# BLUELED.net
KiCad netlist of a schematic drawn in Altium Designer
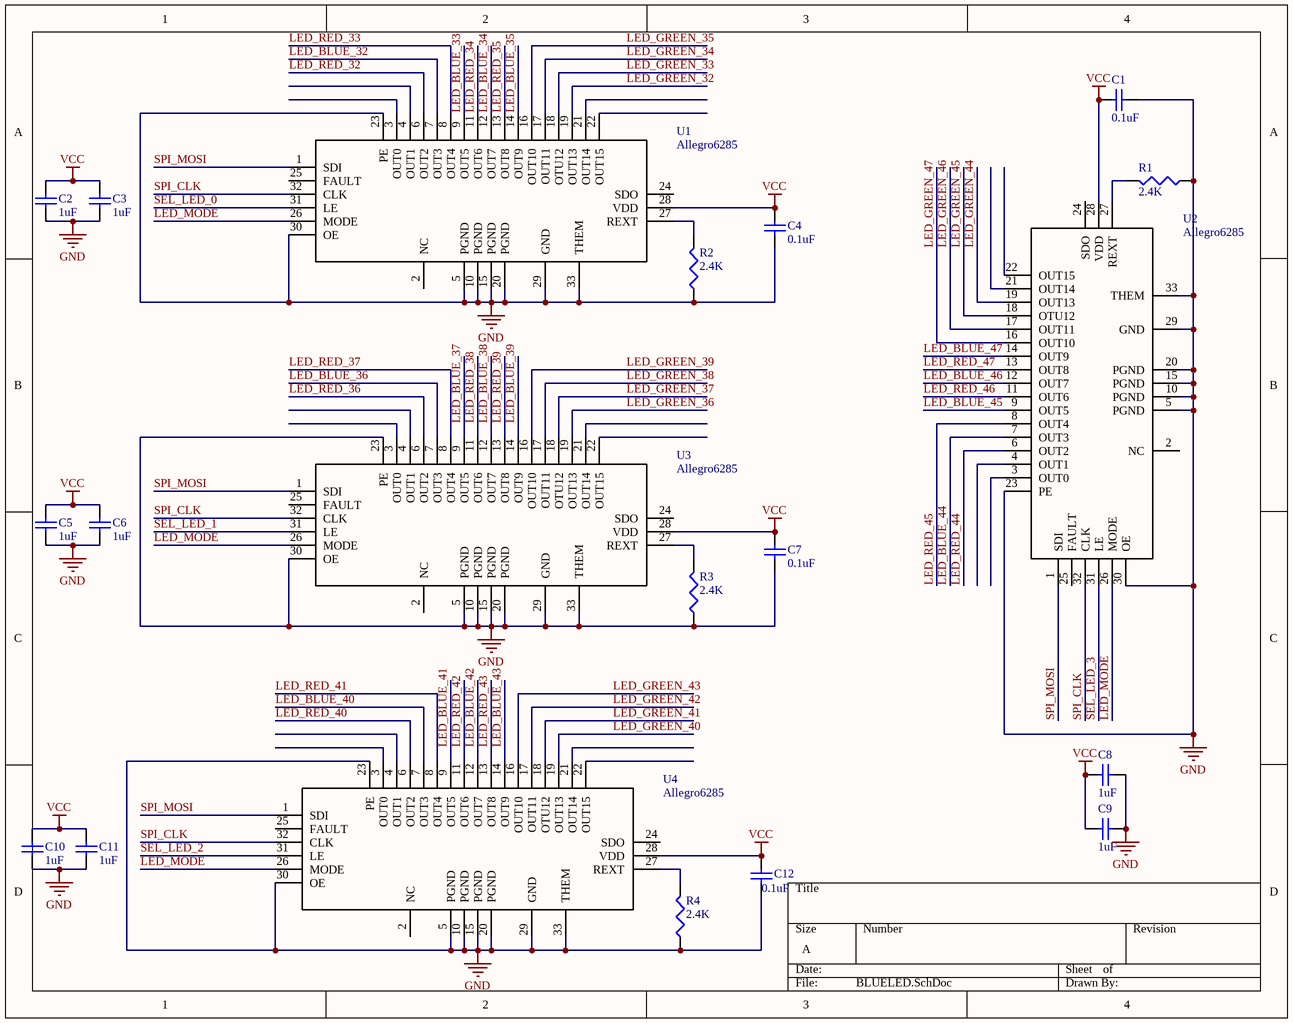
[diagram p0: BLUELED.SchDoc]

(export (version "E")
  (design (tool "Eeschema 10.0.6"))
  (components
    (comp (ref "C1")
      (value "0.1uF")
      (footprint "CAPC1005L")
      (description "Capacitor (Semiconductor SIM Model)")
      (fields (field (name "Comment") "Cap Semi") (field (name "PUBLISHER") "Altium Limited"))
      (libsource (lib "Miscellaneous Devices") (part "Cap Semi"))
    )
    (comp (ref "C2")
      (value "1uF")
      (footprint "CAPC1608L")
      (description "Capacitor (Semiconductor SIM Model)")
      (fields (field (name "Comment") "Cap Semi") (field (name "PUBLISHER") "Altium Limited"))
      (libsource (lib "Miscellaneous Devices") (part "Cap Semi"))
    )
    (comp (ref "C3")
      (value "1uF")
      (footprint "CAPC1608L")
      (description "Capacitor (Semiconductor SIM Model)")
      (fields (field (name "Comment") "Cap Semi") (field (name "PUBLISHER") "Altium Limited"))
      (libsource (lib "Miscellaneous Devices") (part "Cap Semi"))
    )
    (comp (ref "C4")
      (value "0.1uF")
      (footprint "CAPC1005L")
      (description "Capacitor (Semiconductor SIM Model)")
      (fields (field (name "Comment") "Cap Semi") (field (name "PUBLISHER") "Altium Limited"))
      (libsource (lib "Miscellaneous Devices") (part "Cap Semi"))
    )
    (comp (ref "C5")
      (value "1uF")
      (footprint "CAPC1608L")
      (description "Capacitor (Semiconductor SIM Model)")
      (fields (field (name "Comment") "Cap Semi") (field (name "PUBLISHER") "Altium Limited"))
      (libsource (lib "Miscellaneous Devices") (part "Cap Semi"))
    )
    (comp (ref "C6")
      (value "1uF")
      (footprint "CAPC1608L")
      (description "Capacitor (Semiconductor SIM Model)")
      (fields (field (name "Comment") "Cap Semi") (field (name "PUBLISHER") "Altium Limited"))
      (libsource (lib "Miscellaneous Devices") (part "Cap Semi"))
    )
    (comp (ref "C7")
      (value "0.1uF")
      (footprint "CAPC1005L")
      (description "Capacitor (Semiconductor SIM Model)")
      (fields (field (name "Comment") "Cap Semi") (field (name "PUBLISHER") "Altium Limited"))
      (libsource (lib "Miscellaneous Devices") (part "Cap Semi"))
    )
    (comp (ref "C8")
      (value "1uF")
      (footprint "CAPC1608L")
      (description "Capacitor (Semiconductor SIM Model)")
      (fields (field (name "Comment") "Cap Semi") (field (name "PUBLISHER") "Altium Limited"))
      (libsource (lib "Miscellaneous Devices") (part "Cap Semi"))
    )
    (comp (ref "C9")
      (value "1uF")
      (footprint "CAPC1608L")
      (description "Capacitor (Semiconductor SIM Model)")
      (fields (field (name "Comment") "Cap Semi") (field (name "PUBLISHER") "Altium Limited"))
      (libsource (lib "Miscellaneous Devices") (part "Cap Semi"))
    )
    (comp (ref "C10")
      (value "1uF")
      (footprint "CAPC1608L")
      (description "Capacitor (Semiconductor SIM Model)")
      (fields (field (name "Comment") "Cap Semi") (field (name "PUBLISHER") "Altium Limited"))
      (libsource (lib "Miscellaneous Devices") (part "Cap Semi"))
    )
    (comp (ref "C11")
      (value "1uF")
      (footprint "CAPC1608L")
      (description "Capacitor (Semiconductor SIM Model)")
      (fields (field (name "Comment") "Cap Semi") (field (name "PUBLISHER") "Altium Limited"))
      (libsource (lib "Miscellaneous Devices") (part "Cap Semi"))
    )
    (comp (ref "C12")
      (value "0.1uF")
      (footprint "CAPC1005L")
      (description "Capacitor (Semiconductor SIM Model)")
      (fields (field (name "Comment") "Cap Semi") (field (name "PUBLISHER") "Altium Limited"))
      (libsource (lib "Miscellaneous Devices") (part "Cap Semi"))
    )
    (comp (ref "R1")
      (value "2.4K")
      (footprint "RESC1608L")
      (description "Resistor")
      (fields (field (name "Comment") "Res3") (field (name "PUBLISHER") "Altium Limited"))
      (libsource (lib "Miscellaneous Devices") (part "Res3"))
    )
    (comp (ref "R2")
      (value "2.4K")
      (footprint "RESC1608L")
      (description "Resistor")
      (fields (field (name "Comment") "Res3") (field (name "PUBLISHER") "Altium Limited"))
      (libsource (lib "Miscellaneous Devices") (part "Res3"))
    )
    (comp (ref "R3")
      (value "2.4K")
      (footprint "RESC1608L")
      (description "Resistor")
      (fields (field (name "Comment") "Res3") (field (name "PUBLISHER") "Altium Limited"))
      (libsource (lib "Miscellaneous Devices") (part "Res3"))
    )
    (comp (ref "R4")
      (value "2.4K")
      (footprint "RESC1608L")
      (description "Resistor")
      (fields (field (name "Comment") "Res3") (field (name "PUBLISHER") "Altium Limited"))
      (libsource (lib "Miscellaneous Devices") (part "Res3"))
    )
    (comp (ref "U1")
      (value "Allegro6285")
      (footprint "QFN-32")
      (libsource (lib "mrone") (part "Allegro6285"))
    )
    (comp (ref "U2")
      (value "Allegro6285")
      (footprint "QFN-32")
      (libsource (lib "mrone") (part "Allegro6285"))
    )
    (comp (ref "U3")
      (value "Allegro6285")
      (footprint "QFN-32")
      (libsource (lib "mrone") (part "Allegro6285"))
    )
    (comp (ref "U4")
      (value "Allegro6285")
      (footprint "QFN-32")
      (libsource (lib "mrone") (part "Allegro6285"))
    )
  )
  (nets
    (net (code "1") (name "/LED_BLUE_32") (class "Default")
      (node (ref "U1") (pin "7") (pinfunction "OUT3_7") (pintype "passive"))
    )
    (net (code "2") (name "/LED_BLUE_33") (class "Default")
      (node (ref "U1") (pin "9") (pinfunction "OUT5_9") (pintype "passive"))
    )
    (net (code "3") (name "/LED_BLUE_34") (class "Default")
      (node (ref "U1") (pin "12") (pinfunction "OUT7_12") (pintype "passive"))
    )
    (net (code "4") (name "/LED_BLUE_35") (class "Default")
      (node (ref "U1") (pin "14") (pinfunction "OUT9_14") (pintype "passive"))
    )
    (net (code "5") (name "/LED_BLUE_36") (class "Default")
      (node (ref "U3") (pin "7") (pinfunction "OUT3_7") (pintype "passive"))
    )
    (net (code "6") (name "/LED_BLUE_37") (class "Default")
      (node (ref "U3") (pin "9") (pinfunction "OUT5_9") (pintype "passive"))
    )
    (net (code "7") (name "/LED_BLUE_38") (class "Default")
      (node (ref "U3") (pin "12") (pinfunction "OUT7_12") (pintype "passive"))
    )
    (net (code "8") (name "/LED_BLUE_39") (class "Default")
      (node (ref "U3") (pin "14") (pinfunction "OUT9_14") (pintype "passive"))
    )
    (net (code "9") (name "/LED_BLUE_40") (class "Default")
      (node (ref "U4") (pin "7") (pinfunction "OUT3_7") (pintype "passive"))
    )
    (net (code "10") (name "/LED_BLUE_41") (class "Default")
      (node (ref "U4") (pin "9") (pinfunction "OUT5_9") (pintype "passive"))
    )
    (net (code "11") (name "/LED_BLUE_42") (class "Default")
      (node (ref "U4") (pin "12") (pinfunction "OUT7_12") (pintype "passive"))
    )
    (net (code "12") (name "/LED_BLUE_43") (class "Default")
      (node (ref "U4") (pin "14") (pinfunction "OUT9_14") (pintype "passive"))
    )
    (net (code "13") (name "/LED_BLUE_44") (class "Default")
      (node (ref "U2") (pin "7") (pinfunction "OUT3_7") (pintype "passive"))
    )
    (net (code "14") (name "/LED_BLUE_45") (class "Default")
      (node (ref "U2") (pin "9") (pinfunction "OUT5_9") (pintype "passive"))
    )
    (net (code "15") (name "/LED_BLUE_46") (class "Default")
      (node (ref "U2") (pin "12") (pinfunction "OUT7_12") (pintype "passive"))
    )
    (net (code "16") (name "/LED_BLUE_47") (class "Default")
      (node (ref "U2") (pin "14") (pinfunction "OUT9_14") (pintype "passive"))
    )
    (net (code "17") (name "/LED_GREEN_32") (class "Default")
      (node (ref "U1") (pin "19") (pinfunction "OUT13_19") (pintype "passive"))
    )
    (net (code "18") (name "/LED_GREEN_33") (class "Default")
      (node (ref "U1") (pin "18") (pinfunction "OTU12_18") (pintype "passive"))
    )
    (net (code "19") (name "/LED_GREEN_34") (class "Default")
      (node (ref "U1") (pin "17") (pinfunction "OUT11_17") (pintype "passive"))
    )
    (net (code "20") (name "/LED_GREEN_35") (class "Default")
      (node (ref "U1") (pin "16") (pinfunction "OUT10_16") (pintype "passive"))
    )
    (net (code "21") (name "/LED_GREEN_36") (class "Default")
      (node (ref "U3") (pin "19") (pinfunction "OUT13_19") (pintype "passive"))
    )
    (net (code "22") (name "/LED_GREEN_37") (class "Default")
      (node (ref "U3") (pin "18") (pinfunction "OTU12_18") (pintype "passive"))
    )
    (net (code "23") (name "/LED_GREEN_38") (class "Default")
      (node (ref "U3") (pin "17") (pinfunction "OUT11_17") (pintype "passive"))
    )
    (net (code "24") (name "/LED_GREEN_39") (class "Default")
      (node (ref "U3") (pin "16") (pinfunction "OUT10_16") (pintype "passive"))
    )
    (net (code "25") (name "/LED_GREEN_40") (class "Default")
      (node (ref "U4") (pin "19") (pinfunction "OUT13_19") (pintype "passive"))
    )
    (net (code "26") (name "/LED_GREEN_41") (class "Default")
      (node (ref "U4") (pin "18") (pinfunction "OTU12_18") (pintype "passive"))
    )
    (net (code "27") (name "/LED_GREEN_42") (class "Default")
      (node (ref "U4") (pin "17") (pinfunction "OUT11_17") (pintype "passive"))
    )
    (net (code "28") (name "/LED_GREEN_43") (class "Default")
      (node (ref "U4") (pin "16") (pinfunction "OUT10_16") (pintype "passive"))
    )
    (net (code "29") (name "/LED_GREEN_44") (class "Default")
      (node (ref "U2") (pin "19") (pinfunction "OUT13_19") (pintype "passive"))
    )
    (net (code "30") (name "/LED_GREEN_45") (class "Default")
      (node (ref "U2") (pin "18") (pinfunction "OTU12_18") (pintype "passive"))
    )
    (net (code "31") (name "/LED_GREEN_46") (class "Default")
      (node (ref "U2") (pin "17") (pinfunction "OUT11_17") (pintype "passive"))
    )
    (net (code "32") (name "/LED_GREEN_47") (class "Default")
      (node (ref "U2") (pin "16") (pinfunction "OUT10_16") (pintype "passive"))
    )
    (net (code "33") (name "/LED_MODE") (class "Default")
      (node (ref "U1") (pin "26") (pinfunction "MODE_26") (pintype "passive"))
      (node (ref "U2") (pin "26") (pinfunction "MODE_26") (pintype "passive"))
      (node (ref "U3") (pin "26") (pinfunction "MODE_26") (pintype "passive"))
      (node (ref "U4") (pin "26") (pinfunction "MODE_26") (pintype "passive"))
    )
    (net (code "34") (name "/LED_RED_32") (class "Default")
      (node (ref "U1") (pin "6") (pinfunction "OUT2_6") (pintype "passive"))
    )
    (net (code "35") (name "/LED_RED_33") (class "Default")
      (node (ref "U1") (pin "8") (pinfunction "OUT4_8") (pintype "passive"))
    )
    (net (code "36") (name "/LED_RED_34") (class "Default")
      (node (ref "U1") (pin "11") (pinfunction "OUT6_11") (pintype "passive"))
    )
    (net (code "37") (name "/LED_RED_35") (class "Default")
      (node (ref "U1") (pin "13") (pinfunction "OUT8_13") (pintype "passive"))
    )
    (net (code "38") (name "/LED_RED_36") (class "Default")
      (node (ref "U3") (pin "6") (pinfunction "OUT2_6") (pintype "passive"))
    )
    (net (code "39") (name "/LED_RED_37") (class "Default")
      (node (ref "U3") (pin "8") (pinfunction "OUT4_8") (pintype "passive"))
    )
    (net (code "40") (name "/LED_RED_38") (class "Default")
      (node (ref "U3") (pin "11") (pinfunction "OUT6_11") (pintype "passive"))
    )
    (net (code "41") (name "/LED_RED_39") (class "Default")
      (node (ref "U3") (pin "13") (pinfunction "OUT8_13") (pintype "passive"))
    )
    (net (code "42") (name "/LED_RED_40") (class "Default")
      (node (ref "U4") (pin "6") (pinfunction "OUT2_6") (pintype "passive"))
    )
    (net (code "43") (name "/LED_RED_41") (class "Default")
      (node (ref "U4") (pin "8") (pinfunction "OUT4_8") (pintype "passive"))
    )
    (net (code "44") (name "/LED_RED_42") (class "Default")
      (node (ref "U4") (pin "11") (pinfunction "OUT6_11") (pintype "passive"))
    )
    (net (code "45") (name "/LED_RED_43") (class "Default")
      (node (ref "U4") (pin "13") (pinfunction "OUT8_13") (pintype "passive"))
    )
    (net (code "46") (name "/LED_RED_44") (class "Default")
      (node (ref "U2") (pin "6") (pinfunction "OUT2_6") (pintype "passive"))
    )
    (net (code "47") (name "/LED_RED_45") (class "Default")
      (node (ref "U2") (pin "8") (pinfunction "OUT4_8") (pintype "passive"))
    )
    (net (code "48") (name "/LED_RED_46") (class "Default")
      (node (ref "U2") (pin "11") (pinfunction "OUT6_11") (pintype "passive"))
    )
    (net (code "49") (name "/LED_RED_47") (class "Default")
      (node (ref "U2") (pin "13") (pinfunction "OUT8_13") (pintype "passive"))
    )
    (net (code "50") (name "/SEL_LED_0") (class "Default")
      (node (ref "U1") (pin "31") (pinfunction "LE_31") (pintype "passive"))
    )
    (net (code "51") (name "/SEL_LED_1") (class "Default")
      (node (ref "U3") (pin "31") (pinfunction "LE_31") (pintype "passive"))
    )
    (net (code "52") (name "/SEL_LED_2") (class "Default")
      (node (ref "U4") (pin "31") (pinfunction "LE_31") (pintype "passive"))
    )
    (net (code "53") (name "/SEL_LED_3") (class "Default")
      (node (ref "U2") (pin "31") (pinfunction "LE_31") (pintype "passive"))
    )
    (net (code "54") (name "/SPI_CLK") (class "Default")
      (node (ref "U1") (pin "32") (pinfunction "CLK_32") (pintype "passive"))
      (node (ref "U2") (pin "32") (pinfunction "CLK_32") (pintype "passive"))
      (node (ref "U3") (pin "32") (pinfunction "CLK_32") (pintype "passive"))
      (node (ref "U4") (pin "32") (pinfunction "CLK_32") (pintype "passive"))
    )
    (net (code "55") (name "/SPI_MOSI") (class "Default")
      (node (ref "U1") (pin "1") (pinfunction "SDI_1") (pintype "passive"))
      (node (ref "U2") (pin "1") (pinfunction "SDI_1") (pintype "passive"))
      (node (ref "U3") (pin "1") (pinfunction "SDI_1") (pintype "passive"))
      (node (ref "U4") (pin "1") (pinfunction "SDI_1") (pintype "passive"))
    )
    (net (code "56") (name "GND") (class "Default")
      (node (ref "C1") (pin "1") (pinfunction "1_1") (pintype "passive"))
      (node (ref "C10") (pin "1") (pinfunction "1_1") (pintype "passive"))
      (node (ref "C11") (pin "1") (pinfunction "1_1") (pintype "passive"))
      (node (ref "C12") (pin "1") (pinfunction "1_1") (pintype "passive"))
      (node (ref "C2") (pin "1") (pinfunction "1_1") (pintype "passive"))
      (node (ref "C3") (pin "1") (pinfunction "1_1") (pintype "passive"))
      (node (ref "C4") (pin "1") (pinfunction "1_1") (pintype "passive"))
      (node (ref "C5") (pin "1") (pinfunction "1_1") (pintype "passive"))
      (node (ref "C6") (pin "1") (pinfunction "1_1") (pintype "passive"))
      (node (ref "C7") (pin "1") (pinfunction "1_1") (pintype "passive"))
      (node (ref "C8") (pin "1") (pinfunction "1_1") (pintype "passive"))
      (node (ref "C9") (pin "1") (pinfunction "1_1") (pintype "passive"))
      (node (ref "R1") (pin "1") (pinfunction "1_1") (pintype "passive"))
      (node (ref "R2") (pin "1") (pinfunction "1_1") (pintype "passive"))
      (node (ref "R3") (pin "1") (pinfunction "1_1") (pintype "passive"))
      (node (ref "R4") (pin "1") (pinfunction "1_1") (pintype "passive"))
      (node (ref "U1") (pin "10") (pinfunction "PGND_10") (pintype "passive"))
      (node (ref "U1") (pin "15") (pinfunction "PGND_15") (pintype "passive"))
      (node (ref "U1") (pin "20") (pinfunction "PGND_20") (pintype "passive"))
      (node (ref "U1") (pin "23") (pinfunction "PE_23") (pintype "passive"))
      (node (ref "U1") (pin "29") (pinfunction "GND_29") (pintype "passive"))
      (node (ref "U1") (pin "30") (pinfunction "OE_30") (pintype "passive"))
      (node (ref "U1") (pin "33") (pinfunction "THEM_33") (pintype "passive"))
      (node (ref "U1") (pin "5") (pinfunction "PGND_5") (pintype "passive"))
      (node (ref "U2") (pin "10") (pinfunction "PGND_10") (pintype "passive"))
      (node (ref "U2") (pin "15") (pinfunction "PGND_15") (pintype "passive"))
      (node (ref "U2") (pin "20") (pinfunction "PGND_20") (pintype "passive"))
      (node (ref "U2") (pin "23") (pinfunction "PE_23") (pintype "passive"))
      (node (ref "U2") (pin "29") (pinfunction "GND_29") (pintype "passive"))
      (node (ref "U2") (pin "30") (pinfunction "OE_30") (pintype "passive"))
      (node (ref "U2") (pin "33") (pinfunction "THEM_33") (pintype "passive"))
      (node (ref "U2") (pin "5") (pinfunction "PGND_5") (pintype "passive"))
      (node (ref "U3") (pin "10") (pinfunction "PGND_10") (pintype "passive"))
      (node (ref "U3") (pin "15") (pinfunction "PGND_15") (pintype "passive"))
      (node (ref "U3") (pin "20") (pinfunction "PGND_20") (pintype "passive"))
      (node (ref "U3") (pin "23") (pinfunction "PE_23") (pintype "passive"))
      (node (ref "U3") (pin "29") (pinfunction "GND_29") (pintype "passive"))
      (node (ref "U3") (pin "30") (pinfunction "OE_30") (pintype "passive"))
      (node (ref "U3") (pin "33") (pinfunction "THEM_33") (pintype "passive"))
      (node (ref "U3") (pin "5") (pinfunction "PGND_5") (pintype "passive"))
      (node (ref "U4") (pin "10") (pinfunction "PGND_10") (pintype "passive"))
      (node (ref "U4") (pin "15") (pinfunction "PGND_15") (pintype "passive"))
      (node (ref "U4") (pin "20") (pinfunction "PGND_20") (pintype "passive"))
      (node (ref "U4") (pin "23") (pinfunction "PE_23") (pintype "passive"))
      (node (ref "U4") (pin "29") (pinfunction "GND_29") (pintype "passive"))
      (node (ref "U4") (pin "30") (pinfunction "OE_30") (pintype "passive"))
      (node (ref "U4") (pin "33") (pinfunction "THEM_33") (pintype "passive"))
      (node (ref "U4") (pin "5") (pinfunction "PGND_5") (pintype "passive"))
    )
    (net (code "57") (name "Net-(U1-REXT)") (class "Default")
      (node (ref "R2") (pin "2") (pinfunction "2_2") (pintype "passive"))
      (node (ref "U1") (pin "27") (pinfunction "REXT_27") (pintype "passive"))
    )
    (net (code "58") (name "Net-(U2-REXT)") (class "Default")
      (node (ref "R1") (pin "2") (pinfunction "2_2") (pintype "passive"))
      (node (ref "U2") (pin "27") (pinfunction "REXT_27") (pintype "passive"))
    )
    (net (code "59") (name "Net-(U3-REXT)") (class "Default")
      (node (ref "R3") (pin "2") (pinfunction "2_2") (pintype "passive"))
      (node (ref "U3") (pin "27") (pinfunction "REXT_27") (pintype "passive"))
    )
    (net (code "60") (name "Net-(U4-REXT)") (class "Default")
      (node (ref "R4") (pin "2") (pinfunction "2_2") (pintype "passive"))
      (node (ref "U4") (pin "27") (pinfunction "REXT_27") (pintype "passive"))
    )
    (net (code "61") (name "VCC") (class "Default")
      (node (ref "C1") (pin "2") (pinfunction "2_2") (pintype "passive"))
      (node (ref "C10") (pin "2") (pinfunction "2_2") (pintype "passive"))
      (node (ref "C11") (pin "2") (pinfunction "2_2") (pintype "passive"))
      (node (ref "C12") (pin "2") (pinfunction "2_2") (pintype "passive"))
      (node (ref "C2") (pin "2") (pinfunction "2_2") (pintype "passive"))
      (node (ref "C3") (pin "2") (pinfunction "2_2") (pintype "passive"))
      (node (ref "C4") (pin "2") (pinfunction "2_2") (pintype "passive"))
      (node (ref "C5") (pin "2") (pinfunction "2_2") (pintype "passive"))
      (node (ref "C6") (pin "2") (pinfunction "2_2") (pintype "passive"))
      (node (ref "C7") (pin "2") (pinfunction "2_2") (pintype "passive"))
      (node (ref "C8") (pin "2") (pinfunction "2_2") (pintype "passive"))
      (node (ref "C9") (pin "2") (pinfunction "2_2") (pintype "passive"))
      (node (ref "U1") (pin "28") (pinfunction "VDD_28") (pintype "passive"))
      (node (ref "U2") (pin "28") (pinfunction "VDD_28") (pintype "passive"))
      (node (ref "U3") (pin "28") (pinfunction "VDD_28") (pintype "passive"))
      (node (ref "U4") (pin "28") (pinfunction "VDD_28") (pintype "passive"))
    )
    (net (code "62") (name "unconnected-(U1-FAULT-Pad25)") (class "Default")
      (node (ref "U1") (pin "25") (pinfunction "FAULT_25") (pintype "passive"))
    )
    (net (code "63") (name "unconnected-(U1-NC-Pad2)") (class "Default")
      (node (ref "U1") (pin "2") (pinfunction "NC_2") (pintype "passive"))
    )
    (net (code "64") (name "unconnected-(U1-OUT0-Pad3)") (class "Default")
      (node (ref "U1") (pin "3") (pinfunction "OUT0_3") (pintype "passive"))
    )
    (net (code "65") (name "unconnected-(U1-OUT1-Pad4)") (class "Default")
      (node (ref "U1") (pin "4") (pinfunction "OUT1_4") (pintype "passive"))
    )
    (net (code "66") (name "unconnected-(U1-OUT14-Pad21)") (class "Default")
      (node (ref "U1") (pin "21") (pinfunction "OUT14_21") (pintype "passive"))
    )
    (net (code "67") (name "unconnected-(U1-OUT15-Pad22)") (class "Default")
      (node (ref "U1") (pin "22") (pinfunction "OUT15_22") (pintype "passive"))
    )
    (net (code "68") (name "unconnected-(U1-SDO-Pad24)") (class "Default")
      (node (ref "U1") (pin "24") (pinfunction "SDO_24") (pintype "passive"))
    )
    (net (code "69") (name "unconnected-(U2-FAULT-Pad25)") (class "Default")
      (node (ref "U2") (pin "25") (pinfunction "FAULT_25") (pintype "passive"))
    )
    (net (code "70") (name "unconnected-(U2-NC-Pad2)") (class "Default")
      (node (ref "U2") (pin "2") (pinfunction "NC_2") (pintype "passive"))
    )
    (net (code "71") (name "unconnected-(U2-OUT0-Pad3)") (class "Default")
      (node (ref "U2") (pin "3") (pinfunction "OUT0_3") (pintype "passive"))
    )
    (net (code "72") (name "unconnected-(U2-OUT1-Pad4)") (class "Default")
      (node (ref "U2") (pin "4") (pinfunction "OUT1_4") (pintype "passive"))
    )
    (net (code "73") (name "unconnected-(U2-OUT14-Pad21)") (class "Default")
      (node (ref "U2") (pin "21") (pinfunction "OUT14_21") (pintype "passive"))
    )
    (net (code "74") (name "unconnected-(U2-OUT15-Pad22)") (class "Default")
      (node (ref "U2") (pin "22") (pinfunction "OUT15_22") (pintype "passive"))
    )
    (net (code "75") (name "unconnected-(U2-SDO-Pad24)") (class "Default")
      (node (ref "U2") (pin "24") (pinfunction "SDO_24") (pintype "passive"))
    )
    (net (code "76") (name "unconnected-(U3-FAULT-Pad25)") (class "Default")
      (node (ref "U3") (pin "25") (pinfunction "FAULT_25") (pintype "passive"))
    )
    (net (code "77") (name "unconnected-(U3-NC-Pad2)") (class "Default")
      (node (ref "U3") (pin "2") (pinfunction "NC_2") (pintype "passive"))
    )
    (net (code "78") (name "unconnected-(U3-OUT0-Pad3)") (class "Default")
      (node (ref "U3") (pin "3") (pinfunction "OUT0_3") (pintype "passive"))
    )
    (net (code "79") (name "unconnected-(U3-OUT1-Pad4)") (class "Default")
      (node (ref "U3") (pin "4") (pinfunction "OUT1_4") (pintype "passive"))
    )
    (net (code "80") (name "unconnected-(U3-OUT14-Pad21)") (class "Default")
      (node (ref "U3") (pin "21") (pinfunction "OUT14_21") (pintype "passive"))
    )
    (net (code "81") (name "unconnected-(U3-OUT15-Pad22)") (class "Default")
      (node (ref "U3") (pin "22") (pinfunction "OUT15_22") (pintype "passive"))
    )
    (net (code "82") (name "unconnected-(U3-SDO-Pad24)") (class "Default")
      (node (ref "U3") (pin "24") (pinfunction "SDO_24") (pintype "passive"))
    )
    (net (code "83") (name "unconnected-(U4-FAULT-Pad25)") (class "Default")
      (node (ref "U4") (pin "25") (pinfunction "FAULT_25") (pintype "passive"))
    )
    (net (code "84") (name "unconnected-(U4-NC-Pad2)") (class "Default")
      (node (ref "U4") (pin "2") (pinfunction "NC_2") (pintype "passive"))
    )
    (net (code "85") (name "unconnected-(U4-OUT0-Pad3)") (class "Default")
      (node (ref "U4") (pin "3") (pinfunction "OUT0_3") (pintype "passive"))
    )
    (net (code "86") (name "unconnected-(U4-OUT1-Pad4)") (class "Default")
      (node (ref "U4") (pin "4") (pinfunction "OUT1_4") (pintype "passive"))
    )
    (net (code "87") (name "unconnected-(U4-OUT14-Pad21)") (class "Default")
      (node (ref "U4") (pin "21") (pinfunction "OUT14_21") (pintype "passive"))
    )
    (net (code "88") (name "unconnected-(U4-OUT15-Pad22)") (class "Default")
      (node (ref "U4") (pin "22") (pinfunction "OUT15_22") (pintype "passive"))
    )
    (net (code "89") (name "unconnected-(U4-SDO-Pad24)") (class "Default")
      (node (ref "U4") (pin "24") (pinfunction "SDO_24") (pintype "passive"))
    )
  )
)
